# Motor_control.net
KiCad netlist of a schematic drawn in EAGLE
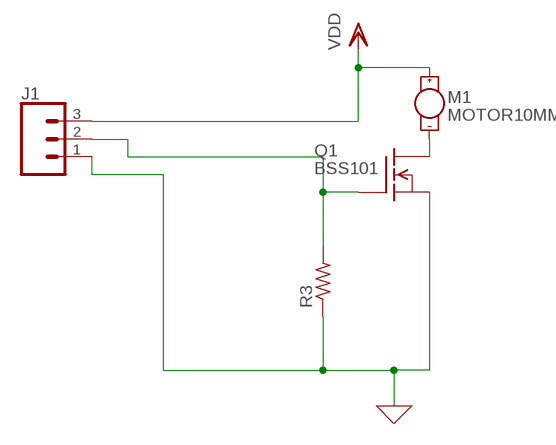
[diagram p0: schematic, sheet 1]

(export (version "E")
  (design (tool "Eeschema 10.0.6"))
  (components
    (comp (ref "J1")
      (value "CONN_03")
      (footprint "eagle-import:1X03")
      (libsource (lib "eagle-import") (part "CONN_03"))
    )
    (comp (ref "M1")
      (value "MOTOR10MM")
      (footprint "eagle-import:VIBE-MOTOR-10MM")
      (libsource (lib "eagle-import") (part "MOTOR10MM"))
    )
    (comp (ref "Q1")
      (value "BSS101")
      (footprint "eagle-import:TO92")
      (libsource (lib "eagle-import") (part "BSS101"))
    )
    (comp (ref "R3")
      (value "R-US_0207/10")
      (footprint "eagle-import:0207_10")
      (libsource (lib "eagle-import") (part "R-US_0207/10"))
    )
  )
  (nets
    (net (code "1") (name "GND") (class "Default")
      (node (ref "J1") (pin "1") (pinfunction "1_1") (pintype "passive"))
      (node (ref "Q1") (pin "1") (pinfunction "S_1") (pintype "passive"))
      (node (ref "R3") (pin "1") (pinfunction "1_1") (pintype "passive"))
    )
    (net (code "2") (name "Net-(Q1-D)") (class "Default")
      (node (ref "M1") (pin "-") (pinfunction "-_-") (pintype "bidirectional"))
      (node (ref "Q1") (pin "3") (pinfunction "D_3") (pintype "passive"))
    )
    (net (code "3") (name "Net-(Q1-G)") (class "Default")
      (node (ref "J1") (pin "2") (pinfunction "2_2") (pintype "passive"))
      (node (ref "Q1") (pin "2") (pinfunction "G_2") (pintype "passive"))
      (node (ref "R3") (pin "2") (pinfunction "2_2") (pintype "passive"))
    )
    (net (code "4") (name "VDD") (class "Default")
      (node (ref "J1") (pin "3") (pinfunction "3_3") (pintype "passive"))
      (node (ref "M1") (pin "+") (pinfunction "+_+") (pintype "bidirectional"))
    )
  )
)
